# Cap_EEPROM.net
KiCad netlist of a schematic drawn in Altium Designer
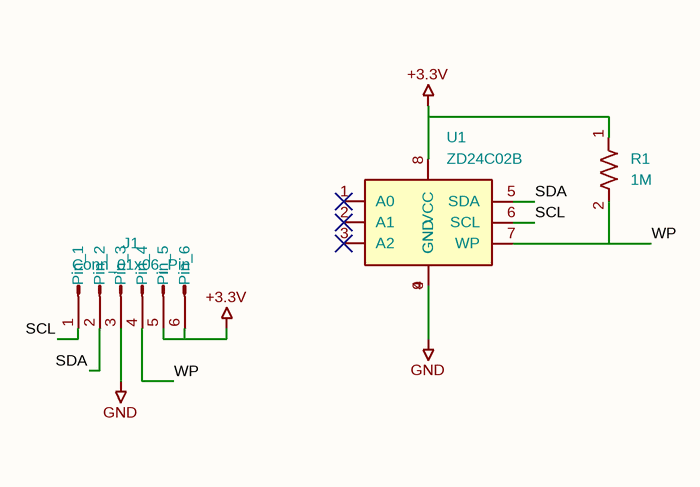
[diagram p0: Cap_EEPROM.SchDoc]

(export (version "E")
  (design (tool "Eeschema 10.0.6"))
  (components
    (comp (ref "J1")
      (value "Conn_01x06_Pin")
      (description "Generic connector, single row, 01x06, script generated")
      (libsource (lib "Connector") (part "Conn_01x06_Pin"))
    )
    (comp (ref "R1")
      (value "1M")
      (description "Resistor, US symbol")
      (libsource (lib "Device") (part "R_US"))
    )
    (comp (ref "U1")
      (value "ZD24C02B")
      (description "I2C Serial EEPROM, 2Kb (256x8), UDFN8")
      (libsource (lib "Memory_EEPROM") (part "AT24CS01-MAHM"))
    )
  )
  (nets
    (net (code "1") (name "+3.3V") (class "Default")
      (node (ref "J1") (pin "5") (pinfunction "Pin_5_5") (pintype "passive"))
      (node (ref "J1") (pin "6") (pinfunction "Pin_6_6") (pintype "passive"))
      (node (ref "R1") (pin "1") (pinfunction "1_1") (pintype "passive"))
      (node (ref "U1") (pin "8") (pinfunction "VCC_8") (pintype "passive"))
    )
    (net (code "2") (name "/SCL") (class "Default")
      (node (ref "J1") (pin "1") (pinfunction "Pin_1_1") (pintype "passive"))
      (node (ref "U1") (pin "6") (pinfunction "SCL_6") (pintype "passive"))
    )
    (net (code "3") (name "/SDA") (class "Default")
      (node (ref "J1") (pin "2") (pinfunction "Pin_2_2") (pintype "passive"))
      (node (ref "U1") (pin "5") (pinfunction "SDA_5") (pintype "passive"))
    )
    (net (code "4") (name "/WP") (class "Default")
      (node (ref "J1") (pin "4") (pinfunction "Pin_4_4") (pintype "passive"))
      (node (ref "R1") (pin "2") (pinfunction "2_2") (pintype "passive"))
      (node (ref "U1") (pin "7") (pinfunction "WP_7") (pintype "passive"))
    )
    (net (code "5") (name "GND") (class "Default")
      (node (ref "J1") (pin "3") (pinfunction "Pin_3_3") (pintype "passive"))
      (node (ref "U1") (pin "4") (pinfunction "GND_4") (pintype "passive"))
      (node (ref "U1") (pin "9") (pinfunction "GND_9") (pintype "passive"))
    )
    (net (code "6") (name "unconnected-(U1-A0-Pad1)") (class "Default")
      (node (ref "U1") (pin "1") (pinfunction "A0_1") (pintype "passive+no_connect"))
    )
    (net (code "7") (name "unconnected-(U1-A1-Pad2)") (class "Default")
      (node (ref "U1") (pin "2") (pinfunction "A1_2") (pintype "passive+no_connect"))
    )
    (net (code "8") (name "unconnected-(U1-A2-Pad3)") (class "Default")
      (node (ref "U1") (pin "3") (pinfunction "A2_3") (pintype "passive+no_connect"))
    )
  )
)
